# ConsoleSchematicFirst.net
KiCad netlist of a schematic drawn in EAGLE
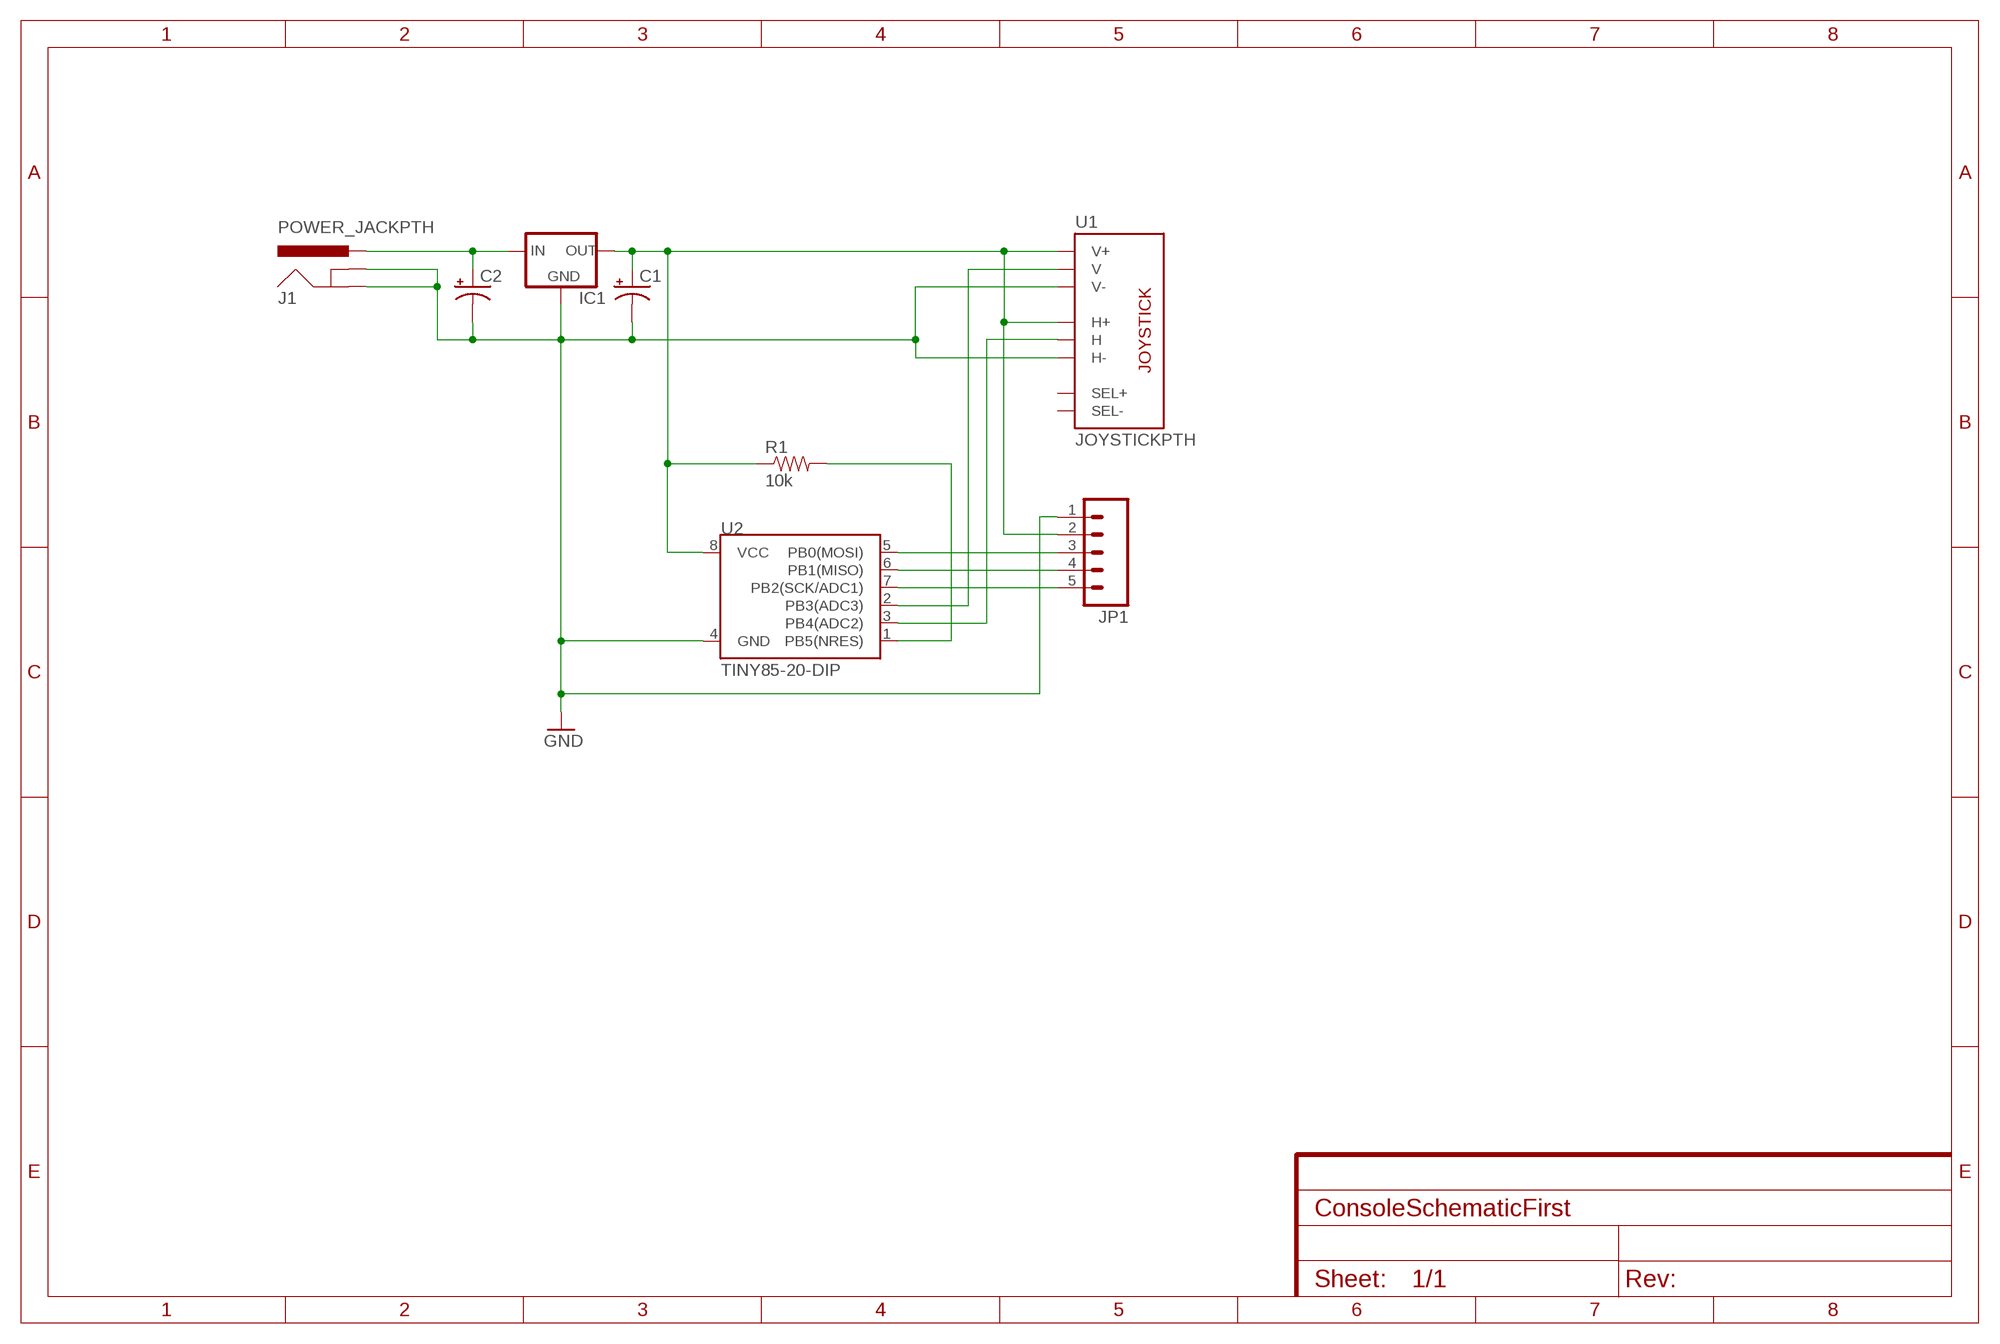
[diagram p0: schematic, sheet 1]

(export (version "E")
  (design (tool "Eeschema 10.0.6"))
  (components
    (comp (ref "C1")
      (value "10UF-25V-20%(PTH)KIT")
      (footprint "eagle-import:CPOL-RADIAL-10UF-25V-KIT")
      (libsource (lib "eagle-import") (part "10UF-25V-20%(PTH)KIT"))
    )
    (comp (ref "C2")
      (value "10UF-25V-20%(PTH)KIT")
      (footprint "eagle-import:CPOL-RADIAL-10UF-25V-KIT")
      (libsource (lib "eagle-import") (part "10UF-25V-20%(PTH)KIT"))
    )
    (comp (ref "IC1")
      (value "V_REG_78XXSIDE")
      (footprint "eagle-import:78XXL")
      (libsource (lib "eagle-import") (part "V_REG_78XXSIDE"))
    )
    (comp (ref "J1")
      (value "POWER_JACKPTH")
      (footprint "eagle-import:POWER_JACK_PTH")
      (libsource (lib "eagle-import") (part "POWER_JACKPTH"))
    )
    (comp (ref "JP1")
      (value "M05LOCK")
      (footprint "eagle-import:1X05_LOCK")
      (libsource (lib "eagle-import") (part "M05LOCK"))
    )
    (comp (ref "R1")
      (value "10k")
      (footprint "eagle-import:AXIAL-0.3")
      (libsource (lib "eagle-import") (part "10KOHM-1/4W-1%(PTH)HORIZ"))
    )
    (comp (ref "U1")
      (value "JOYSTICKPTH")
      (footprint "eagle-import:JOYSTICK")
      (libsource (lib "eagle-import") (part "JOYSTICKPTH"))
    )
    (comp (ref "U2")
      (value "TINY85-20-DIP")
      (footprint "eagle-import:DIP08")
      (libsource (lib "eagle-import") (part "ATTINY45TINY85-20-DIP"))
    )
  )
  (nets
    (net (code "1") (name "GND") (class "Default")
      (node (ref "C1") (pin "2") (pinfunction "-_2") (pintype "passive"))
      (node (ref "C2") (pin "2") (pinfunction "-_2") (pintype "passive"))
      (node (ref "IC1") (pin "GND") (pinfunction "GND_GND") (pintype "input"))
      (node (ref "J1") (pin "GND") (pinfunction "GND_GND") (pintype "bidirectional"))
      (node (ref "J1") (pin "GNDBREAK") (pinfunction "GNDBREAK_GNDBREAK") (pintype "bidirectional"))
      (node (ref "JP1") (pin "1") (pinfunction "1_1") (pintype "passive"))
      (node (ref "U1") (pin "H3") (pinfunction "H-_H3") (pintype "bidirectional"))
      (node (ref "U1") (pin "V3") (pinfunction "V-_V3") (pintype "bidirectional"))
      (node (ref "U2") (pin "4") (pinfunction "GND_4") (pintype "bidirectional"))
    )
    (net (code "2") (name "Net-(C1-+)") (class "Default")
      (node (ref "C1") (pin "1") (pinfunction "+_1") (pintype "passive"))
      (node (ref "IC1") (pin "OUT") (pinfunction "OUT_OUT") (pintype "output"))
      (node (ref "JP1") (pin "2") (pinfunction "2_2") (pintype "passive"))
      (node (ref "R1") (pin "P$1") (pinfunction "1_P$1") (pintype "passive"))
      (node (ref "U1") (pin "H1") (pinfunction "H+_H1") (pintype "bidirectional"))
      (node (ref "U1") (pin "V1") (pinfunction "V+_V1") (pintype "bidirectional"))
      (node (ref "U2") (pin "8") (pinfunction "VCC_8") (pintype "bidirectional"))
    )
    (net (code "3") (name "Net-(C2-+)") (class "Default")
      (node (ref "C2") (pin "1") (pinfunction "+_1") (pintype "passive"))
      (node (ref "IC1") (pin "IN") (pinfunction "IN_IN") (pintype "input"))
      (node (ref "J1") (pin "PWR") (pinfunction "PWR_PWR") (pintype "bidirectional"))
    )
    (net (code "4") (name "Net-(R1-2)") (class "Default")
      (node (ref "R1") (pin "P$2") (pinfunction "2_P$2") (pintype "passive"))
      (node (ref "U2") (pin "1") (pinfunction "PB5(NRES)_1") (pintype "bidirectional"))
    )
    (net (code "5") (name "Net-(U1-H)") (class "Default")
      (node (ref "U1") (pin "H2") (pinfunction "H_H2") (pintype "bidirectional"))
      (node (ref "U2") (pin "3") (pinfunction "PB4(ADC2)_3") (pintype "bidirectional"))
    )
    (net (code "6") (name "Net-(U1-V)") (class "Default")
      (node (ref "U1") (pin "V2") (pinfunction "V_V2") (pintype "bidirectional"))
      (node (ref "U2") (pin "2") (pinfunction "PB3(ADC3)_2") (pintype "bidirectional"))
    )
    (net (code "7") (name "Net-(U2-PB0(MOSI))") (class "Default")
      (node (ref "JP1") (pin "3") (pinfunction "3_3") (pintype "passive"))
      (node (ref "U2") (pin "5") (pinfunction "PB0(MOSI)_5") (pintype "bidirectional"))
    )
    (net (code "8") (name "Net-(U2-PB1(MISO))") (class "Default")
      (node (ref "JP1") (pin "4") (pinfunction "4_4") (pintype "passive"))
      (node (ref "U2") (pin "6") (pinfunction "PB1(MISO)_6") (pintype "bidirectional"))
    )
    (net (code "9") (name "Net-(U2-PB2(SCK{slash}ADC1))") (class "Default")
      (node (ref "JP1") (pin "5") (pinfunction "5_5") (pintype "passive"))
      (node (ref "U2") (pin "7") (pinfunction "PB2(SCK/ADC1)_7") (pintype "bidirectional"))
    )
    (net (code "10") (name "unconnected-(U1-SEL+-PadB1A)") (class "Default")
      (node (ref "U1") (pin "B1A") (pinfunction "SEL+_B1A") (pintype "bidirectional"))
    )
    (net (code "11") (name "unconnected-(U1-SEL--PadB2A)") (class "Default")
      (node (ref "U1") (pin "B2A") (pinfunction "SEL-_B2A") (pintype "bidirectional"))
    )
  )
)
